# SH1_-_POWER.net
KiCad netlist of a schematic drawn in Altium Designer
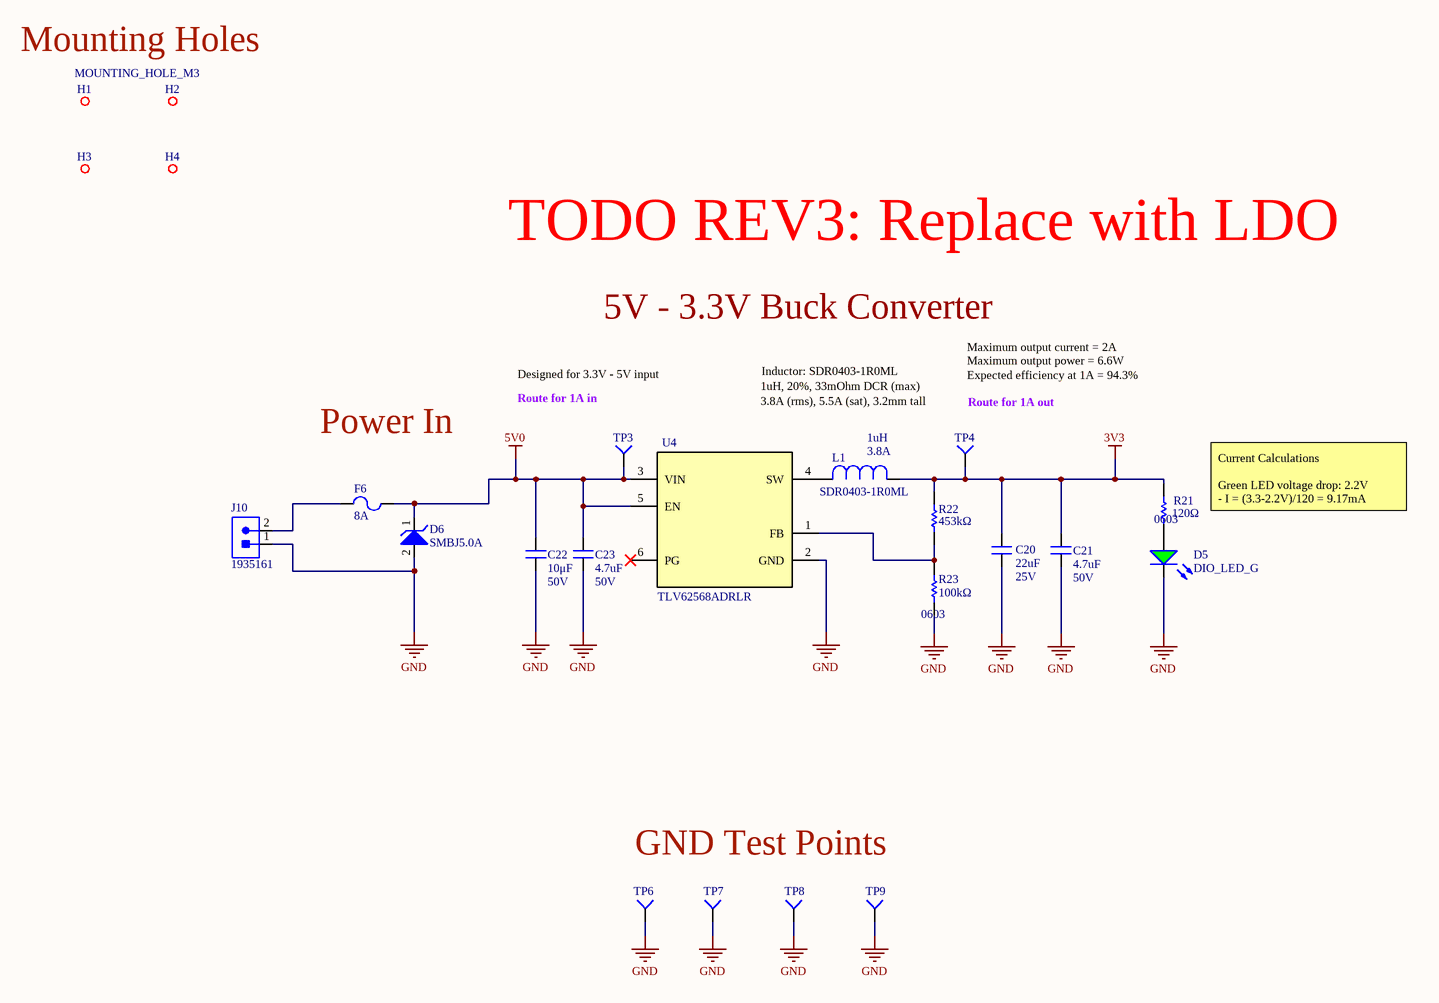
[diagram p0: SH1 - POWER.SchDoc]

(export (version "E")
  (design (tool "Eeschema 10.0.6"))
  (components
    (comp (ref "C20")
      (value "CAP_22uF_25V_1210")
      (footprint "CAPC3225X270N")
      (description "CAP CER 22UF 25V X7R 1210")
      (fields (field (name "VOLTAGE") "25V") (field (name "CAPACITANCE") "22uF"))
      (libsource (lib "UWRT_Schematic_Library_2020") (part "CAP_22uF_25V_1210"))
    )
    (comp (ref "C21")
      (value "CAP_4.7uF_50V_1206")
      (footprint "CAP1206")
      (description "CAP CER 4.7UF 50V X7R 1206")
      (fields (field (name "CAPACITANCE") "4.7uF") (field (name "VOLTAGE") "50V"))
      (libsource (lib "UWRT_Schematic_Library_2020") (part "CAP_4.7uF_50V_1206"))
    )
    (comp (ref "C22")
      (value "10μF")
      (footprint "CAP1206")
      (description "CAP CER 10UF 50V X5R 1206")
      (fields (field (name "VOLTAGE RATING") "50V") (field (name "Comment") "CAP_10uF_50V_1206"))
      (libsource (lib "UWRT_Schematic_Library_2020") (part "CAP_10uF_50V_1206"))
    )
    (comp (ref "C23")
      (value "CAP_4.7uF_50V_1206")
      (footprint "CAP1206")
      (description "CAP CER 4.7UF 50V X7R 1206")
      (fields (field (name "CAPACITANCE") "4.7uF") (field (name "VOLTAGE") "50V"))
      (libsource (lib "UWRT_Schematic_Library_2020") (part "CAP_4.7uF_50V_1206"))
    )
    (comp (ref "D5")
      (value "DIO_LED_G")
      (footprint "LED_0805_GREEN")
      (description "LED GREEN DIFFUSED 0805 SMD")
      (libsource (lib "UWRT_Schematic_Library_2020") (part "DIO_LED_G"))
    )
    (comp (ref "D6")
      (value "TVS_DIODE_UNIDIR_5V")
      (footprint "SMBJ5.0A")
      (description "TVS DIODE 5V 9.2V DO214AA")
      (fields (field (name "MANUFACTURER PART NUMBER 1") "SMBJ5.0A"))
      (libsource (lib "UWRT_Schematic_Library_2020") (part "TVS_DIODE_UNIDIR_5V"))
    )
    (comp (ref "F6")
      (value "FUSE_8A_1206")
      (footprint "FUSE_1206")
      (description "FUSE SMD 8A 24V")
      (fields (field (name "CURRENT RATING") "8A") (field (name "LCSC PART #") "C311032"))
      (libsource (lib "UWRT_Schematic_Library_2020") (part "FUSE_8A_1206"))
    )
    (comp (ref "H1")
      (value "MOUNTING_HOLE_M3")
      (footprint "MOUNTING_HOLE_3mm_SCIENCE_REV2")
      (description "MOUNTING_HOLE_M3 Science Rev2")
      (libsource (lib "UWRT_Schematic_Library_2020") (part "MOUNTING_HOLE_M3_SCIENCE_REV2"))
    )
    (comp (ref "H2")
      (value "MOUNTING_HOLE_M3")
      (footprint "MOUNTING_HOLE_3mm_SCIENCE_REV2")
      (description "MOUNTING_HOLE_M3 Science Rev2")
      (libsource (lib "UWRT_Schematic_Library_2020") (part "MOUNTING_HOLE_M3_SCIENCE_REV2"))
    )
    (comp (ref "H3")
      (value "MOUNTING_HOLE_M3")
      (footprint "MOUNTING_HOLE_3mm_SCIENCE_REV2")
      (description "MOUNTING_HOLE_M3 Science Rev2")
      (libsource (lib "UWRT_Schematic_Library_2020") (part "MOUNTING_HOLE_M3_SCIENCE_REV2"))
    )
    (comp (ref "H4")
      (value "MOUNTING_HOLE_M3")
      (footprint "MOUNTING_HOLE_3mm_SCIENCE_REV2")
      (description "MOUNTING_HOLE_M3 Science Rev2")
      (libsource (lib "UWRT_Schematic_Library_2020") (part "MOUNTING_HOLE_M3_SCIENCE_REV2"))
    )
    (comp (ref "J10")
      (value "CON_2M_TERM")
      (footprint "1935161")
      (description "TERM BLK 2POS SIDE ENTRY 5MM")
      (fields (field (name "VOLTAGE") "300V") (field (name "MANUFACTURER PART NUMBER 1") "1935161"))
      (libsource (lib "UWRT_Schematic_Library_2020") (part "CON_2M_TERM"))
    )
    (comp (ref "L1")
      (value "1uH")
      (footprint "IND_BOURNS_SDR04")
      (description "FIXED IND 1UH 3.8A 33 MOHM SMD")
      (fields
        (field (name "MANUFACTURER PART NUMBER 1") "SDR0403-1R0ML")
        (field (name "TOLERANCE") "±20%")
        (field (name "CURRENT RATING") "3.8A")
        (field (name "Comment") "IND_1uH_3.8A")
      )
      (libsource (lib "UWRT_Schematic_Library_2020") (part "IND_1uH_3.8A"))
    )
    (comp (ref "R21")
      (value "120Ω")
      (footprint "RESC0603")
      (description "RES 120 OHM 5% 1/10W 0603")
      (fields (field (name "PACKAGE/FOOTPRINT") "0603") (field (name "Comment") "RES_120Ω_0603"))
      (libsource (lib "UWRT_Schematic_Library_2020") (part "RES_120Ω_0603_5%"))
    )
    (comp (ref "R22")
      (value "453kΩ")
      (footprint "RESC0603")
      (description "RES 453K OHM 1% 1/10W 0603")
      (fields (field (name "TOLERANCE") "1%") (field (name "Comment") "RES_453kΩ_0603_1%"))
      (libsource (lib "UWRT_Schematic_Library_2020") (part "RES_453kΩ_0603_1%"))
    )
    (comp (ref "R23")
      (value "100kΩ")
      (footprint "RESC0603(1608)_N")
      (description "RES 100K OHM 1% 1/10W 0603")
      (fields
        (field (name "TOLERANCE") "1%")
        (field (name "PACKAGE/FOOTPRINT") "0603")
        (field (name "Comment") "RES_100kΩ_0603_1%")
      )
      (libsource (lib "UWRT_Schematic_Library_2020") (part "RES_100kΩ_0603_1%"))
    )
    (comp (ref "TP3")
      (value "TESTPOINT_SMD_LOOP")
      (footprint "S1751-46R")
      (description "PC TEST POINT SMD")
      (libsource (lib "UWRT_Schematic_Library_2020") (part "TESTPOINT_SMD_LOOP"))
    )
    (comp (ref "TP4")
      (value "TESTPOINT_SMD_LOOP")
      (footprint "S1751-46R")
      (description "PC TEST POINT SMD")
      (libsource (lib "UWRT_Schematic_Library_2020") (part "TESTPOINT_SMD_LOOP"))
    )
    (comp (ref "TP6")
      (value "TESTPOINT_SMD_LOOP")
      (footprint "S1751-46R")
      (description "PC TEST POINT SMD")
      (libsource (lib "UWRT_Schematic_Library_2020") (part "TESTPOINT_SMD_LOOP"))
    )
    (comp (ref "TP7")
      (value "TESTPOINT_1MM_SQUARE")
      (footprint "TESTPOINT_SQUARE_1MM")
      (description "TESTPOINT 1MM SQUARE")
      (libsource (lib "UWRT_Schematic_Library_2020") (part "TESTPOINT_1MM_SQUARE"))
    )
    (comp (ref "TP8")
      (value "TESTPOINT_1MM_SQUARE")
      (footprint "TESTPOINT_SQUARE_1MM")
      (description "TESTPOINT 1MM SQUARE")
      (libsource (lib "UWRT_Schematic_Library_2020") (part "TESTPOINT_1MM_SQUARE"))
    )
    (comp (ref "TP9")
      (value "TESTPOINT_1MM_SQUARE")
      (footprint "TESTPOINT_SQUARE_1MM")
      (description "TESTPOINT 1MM SQUARE")
      (libsource (lib "UWRT_Schematic_Library_2020") (part "TESTPOINT_1MM_SQUARE"))
    )
    (comp (ref "U4")
      (value "TLV62568ADRLR")
      (footprint "SOT50P160X60-6N")
      (description "IC REG BUCK ADJUSTABLE 2A SOT563")
      (libsource (lib "UWRT_Schematic_Library_2020") (part "TLV62568ADRLR"))
    )
  )
  (nets
    (net (code "1") (name "3V3") (class "Default")
      (node (ref "C20") (pin "2") (pinfunction "2_2") (pintype "passive"))
      (node (ref "C21") (pin "2") (pinfunction "2_2") (pintype "passive"))
      (node (ref "L1") (pin "2") (pinfunction "2_2") (pintype "passive"))
      (node (ref "R21") (pin "2") (pinfunction "2_2") (pintype "passive"))
      (node (ref "R22") (pin "2") (pinfunction "2_2") (pintype "passive"))
      (node (ref "TP4") (pin "1") (pinfunction "=value_1") (pintype "passive"))
    )
    (net (code "2") (name "5V0") (class "Default")
      (node (ref "C22") (pin "2") (pinfunction "2_2") (pintype "passive"))
      (node (ref "C23") (pin "2") (pinfunction "2_2") (pintype "passive"))
      (node (ref "D6") (pin "1") (pinfunction "1_1") (pintype "passive"))
      (node (ref "F6") (pin "2") (pinfunction "2_2") (pintype "passive"))
      (node (ref "TP3") (pin "1") (pinfunction "=value_1") (pintype "passive"))
      (node (ref "U4") (pin "3") (pinfunction "VIN_3") (pintype "power_in"))
      (node (ref "U4") (pin "5") (pinfunction "EN_5") (pintype "passive"))
    )
    (net (code "3") (name "GND") (class "Default")
      (node (ref "C20") (pin "1") (pinfunction "1_1") (pintype "passive"))
      (node (ref "C21") (pin "1") (pinfunction "1_1") (pintype "passive"))
      (node (ref "C22") (pin "1") (pinfunction "1_1") (pintype "passive"))
      (node (ref "C23") (pin "1") (pinfunction "1_1") (pintype "passive"))
      (node (ref "D5") (pin "2") (pinfunction "K_2") (pintype "passive"))
      (node (ref "D6") (pin "2") (pinfunction "2_2") (pintype "passive"))
      (node (ref "J10") (pin "1") (pinfunction "1_1") (pintype "passive"))
      (node (ref "R23") (pin "1") (pinfunction "1_1") (pintype "passive"))
      (node (ref "TP6") (pin "1") (pinfunction "=value_1") (pintype "passive"))
      (node (ref "TP7") (pin "1") (pinfunction "=value_1") (pintype "passive"))
      (node (ref "TP8") (pin "1") (pinfunction "=value_1") (pintype "passive"))
      (node (ref "TP9") (pin "1") (pinfunction "=value_1") (pintype "passive"))
      (node (ref "U4") (pin "2") (pinfunction "GND_2") (pintype "power_in"))
    )
    (net (code "4") (name "Net-(D5-A)") (class "Default")
      (node (ref "D5") (pin "1") (pinfunction "A_1") (pintype "passive"))
      (node (ref "R21") (pin "1") (pinfunction "1_1") (pintype "passive"))
    )
    (net (code "5") (name "Net-(F6-Pad1)") (class "Default")
      (node (ref "F6") (pin "1") (pinfunction "1_1") (pintype "passive"))
      (node (ref "J10") (pin "2") (pinfunction "2_2") (pintype "passive"))
    )
    (net (code "6") (name "Net-(U4-FB)") (class "Default")
      (node (ref "R22") (pin "1") (pinfunction "1_1") (pintype "passive"))
      (node (ref "R23") (pin "2") (pinfunction "2_2") (pintype "passive"))
      (node (ref "U4") (pin "1") (pinfunction "FB_1") (pintype "passive"))
    )
    (net (code "7") (name "Net-(U4-SW)") (class "Default")
      (node (ref "L1") (pin "1") (pinfunction "1_1") (pintype "passive"))
      (node (ref "U4") (pin "4") (pinfunction "SW_4") (pintype "power_in"))
    )
    (net (code "8") (name "unconnected-(U4-PG-Pad6)") (class "Default")
      (node (ref "U4") (pin "6") (pinfunction "PG_6") (pintype "open_collector+no_connect"))
    )
  )
)
